# untitled.net
KiCad netlist of a schematic drawn in EAGLE
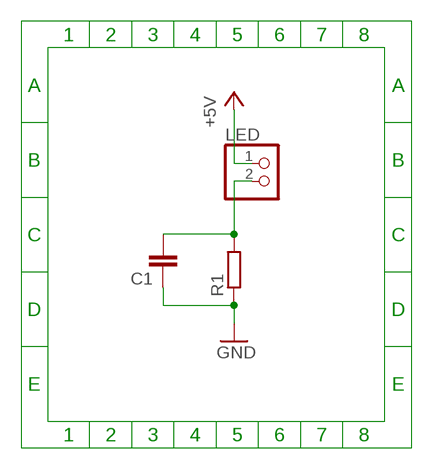
[diagram p0: schematic, sheet 1]

(export (version "E")
  (design (tool "Eeschema 10.0.6"))
  (components
    (comp (ref "C1")
      (value "C-EU025-040X050")
      (footprint "eagle-import:C025-040X050")
      (libsource (lib "eagle-import") (part "C-EU025-040X050"))
    )
    (comp (ref "LED")
      (value "PINHD-1X2")
      (footprint "eagle-import:1X02")
      (libsource (lib "eagle-import") (part "PINHD-1X2"))
    )
    (comp (ref "R1")
      (value "R-EU_0204/7")
      (footprint "eagle-import:0204_7")
      (libsource (lib "eagle-import") (part "R-EU_0204/7"))
    )
  )
  (nets
    (net (code "1") (name "+5V") (class "Default")
      (node (ref "LED") (pin "1") (pinfunction "1_1") (pintype "passive"))
    )
    (net (code "2") (name "GND") (class "Default")
      (node (ref "C1") (pin "1") (pinfunction "1_1") (pintype "passive"))
      (node (ref "R1") (pin "1") (pinfunction "1_1") (pintype "passive"))
    )
    (net (code "3") (name "Net-(C1-Pad2)") (class "Default")
      (node (ref "C1") (pin "2") (pinfunction "2_2") (pintype "passive"))
      (node (ref "LED") (pin "2") (pinfunction "2_2") (pintype "passive"))
      (node (ref "R1") (pin "2") (pinfunction "2_2") (pintype "passive"))
    )
  )
)
